# VL53L0X_Grove_Adapter.net
KiCad netlist of a schematic drawn in EAGLE
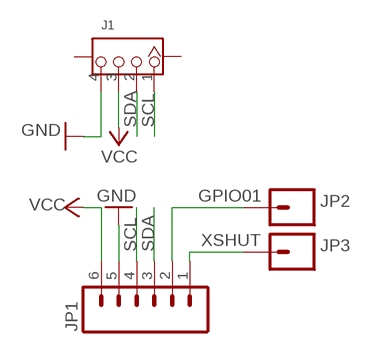
[diagram p0: schematic, sheet 1]

(export (version "E")
  (design (tool "Eeschema 10.0.6"))
  (components
    (comp (ref "J1")
      (value "GROVE-CONNECTOR-4PINHW4-PTH-2.0")
      (footprint "eagle-import:HW4-PTH-2.0")
      (libsource (lib "eagle-import") (part "GROVE-CONNECTOR-4PINHW4-PTH-2.0"))
    )
    (comp (ref "JP1")
      (value "M06SIP")
      (footprint "eagle-import:1X06")
      (libsource (lib "eagle-import") (part "M06SIP"))
    )
    (comp (ref "JP2")
      (value "GPIO01")
      (footprint "eagle-import:1X01")
      (libsource (lib "eagle-import") (part "M01PTH"))
    )
    (comp (ref "JP3")
      (value "XSHUT")
      (footprint "eagle-import:1X01")
      (libsource (lib "eagle-import") (part "M01PTH"))
    )
  )
  (nets
    (net (code "1") (name "/SCL") (class "Default")
      (node (ref "J1") (pin "1") (pinfunction "1_1") (pintype "bidirectional"))
      (node (ref "JP1") (pin "4") (pinfunction "4_4") (pintype "passive"))
    )
    (net (code "2") (name "/SDA") (class "Default")
      (node (ref "J1") (pin "2") (pinfunction "2_2") (pintype "bidirectional"))
      (node (ref "JP1") (pin "3") (pinfunction "3_3") (pintype "passive"))
    )
    (net (code "3") (name "GND") (class "Default")
      (node (ref "J1") (pin "4") (pinfunction "4_4") (pintype "bidirectional"))
      (node (ref "JP1") (pin "5") (pinfunction "5_5") (pintype "passive"))
    )
    (net (code "4") (name "Net-(JP1-Pad1)") (class "Default")
      (node (ref "JP1") (pin "1") (pinfunction "1_1") (pintype "passive"))
      (node (ref "JP3") (pin "1") (pinfunction "1_1") (pintype "passive"))
    )
    (net (code "5") (name "Net-(JP1-Pad2)") (class "Default")
      (node (ref "JP1") (pin "2") (pinfunction "2_2") (pintype "passive"))
      (node (ref "JP2") (pin "1") (pinfunction "1_1") (pintype "passive"))
    )
    (net (code "6") (name "VCC") (class "Default")
      (node (ref "J1") (pin "3") (pinfunction "3_3") (pintype "bidirectional"))
      (node (ref "JP1") (pin "6") (pinfunction "6_6") (pintype "passive"))
    )
    (net (code "7") (name "unconnected-(J1-SS1-Pad5)") (class "Default")
      (node (ref "J1") (pin "5") (pinfunction "SS1_5") (pintype "bidirectional"))
    )
    (net (code "8") (name "unconnected-(J1-SS2-Pad6)") (class "Default")
      (node (ref "J1") (pin "6") (pinfunction "SS2_6") (pintype "bidirectional"))
    )
  )
)
